# CFA_T_4L_B.net
KiCad netlist of a schematic drawn in EAGLE
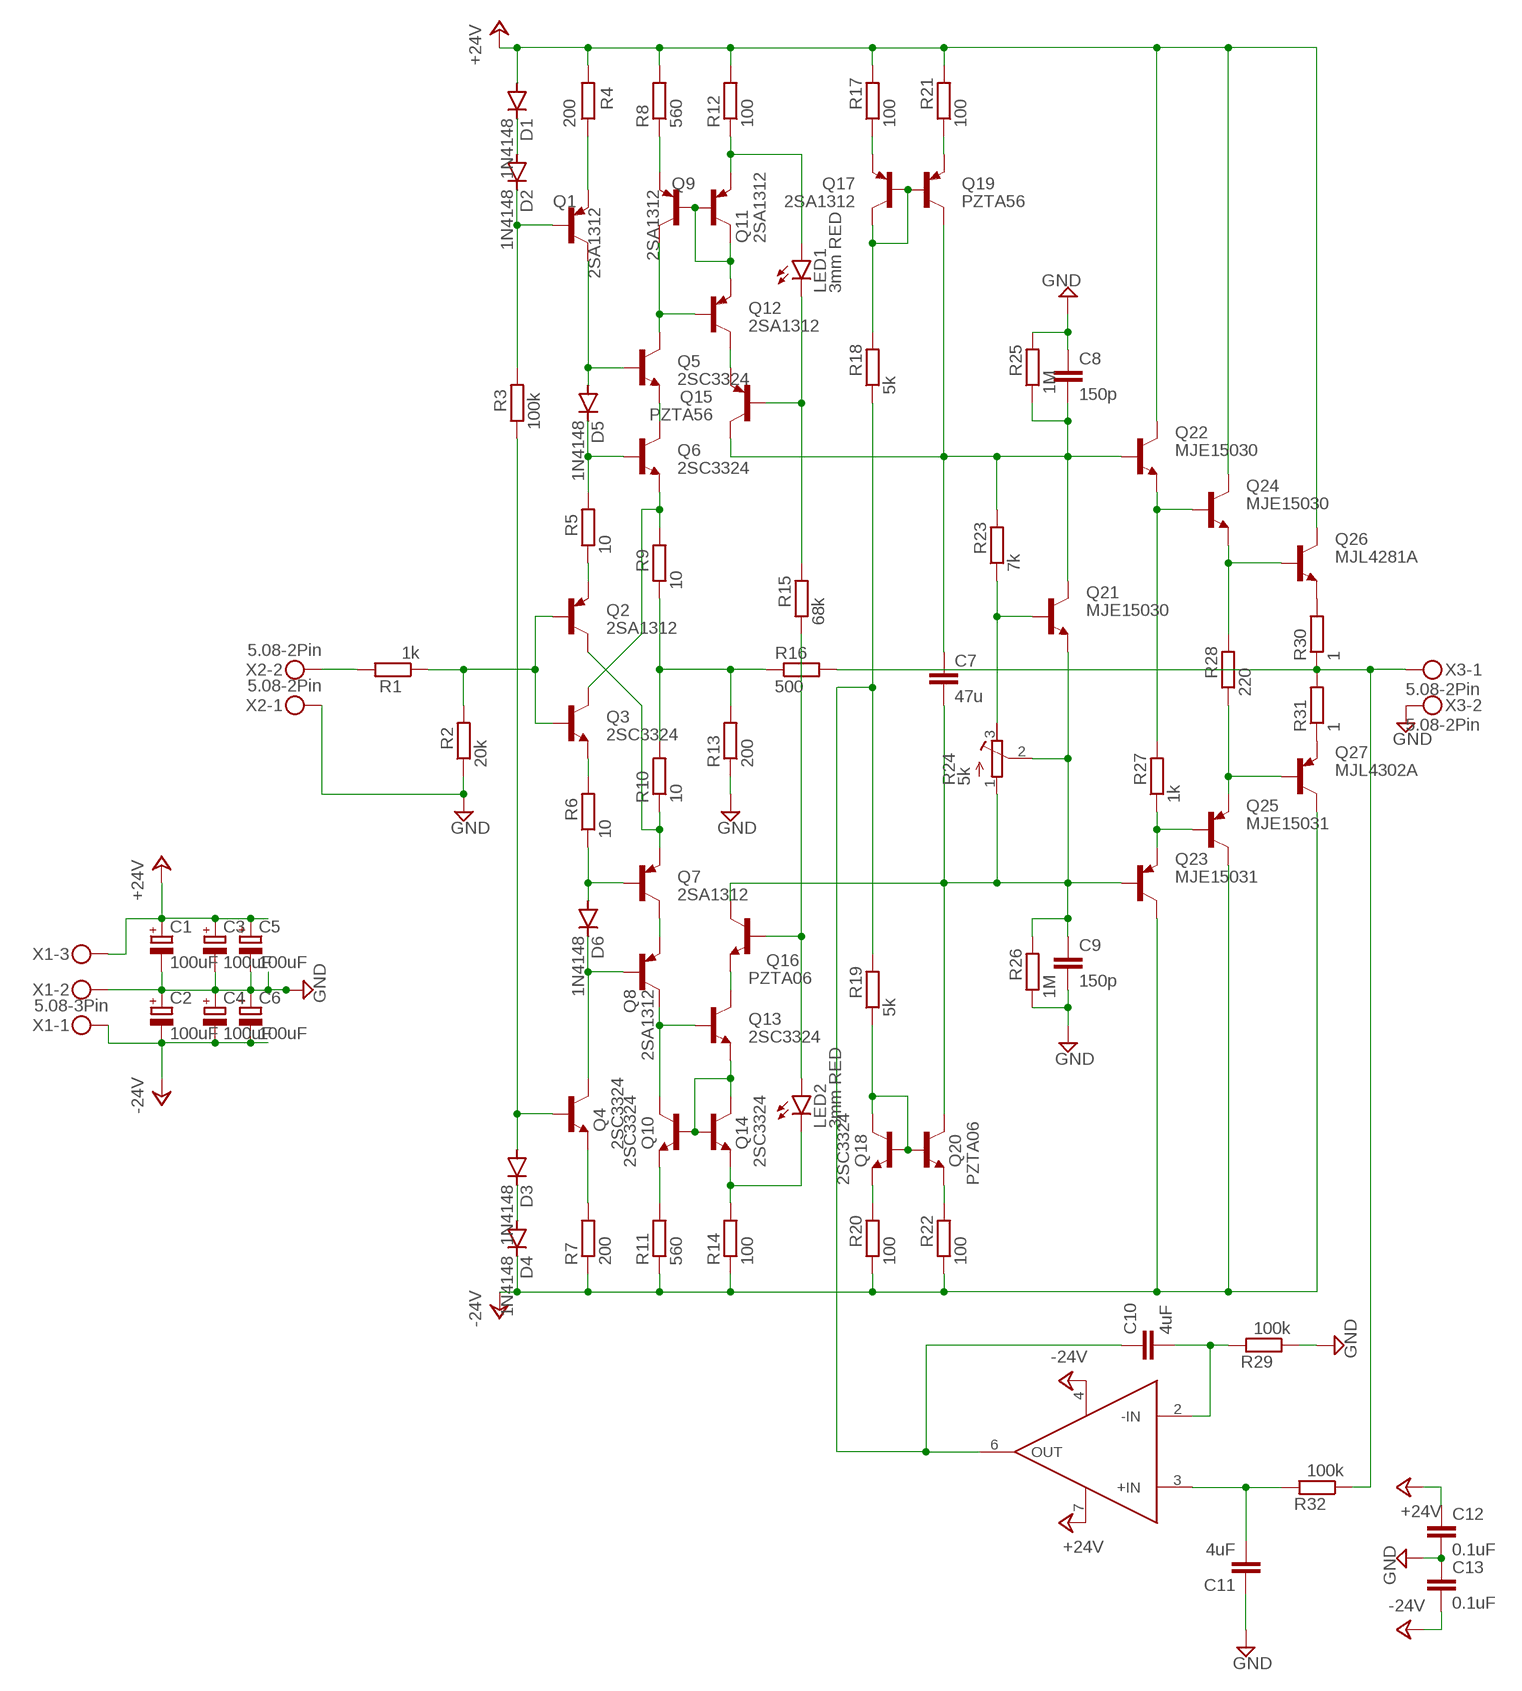
[diagram p0: schematic, sheet 1]

(export (version "E")
  (design (tool "Eeschema 10.0.6"))
  (components
    (comp (ref "C1")
      (value "100uF")
      (footprint "eagle-import:E3,5-8")
      (libsource (lib "eagle-import") (part "CPOL-EUE3.5-8"))
    )
    (comp (ref "C2")
      (value "100uF")
      (footprint "eagle-import:E3,5-8")
      (libsource (lib "eagle-import") (part "CPOL-EUE3.5-8"))
    )
    (comp (ref "C3")
      (value "100uF")
      (footprint "eagle-import:E3,5-8")
      (libsource (lib "eagle-import") (part "CPOL-EUE3.5-8"))
    )
    (comp (ref "C4")
      (value "100uF")
      (footprint "eagle-import:E3,5-8")
      (libsource (lib "eagle-import") (part "CPOL-EUE3.5-8"))
    )
    (comp (ref "C5")
      (value "100uF")
      (footprint "eagle-import:E3,5-8")
      (libsource (lib "eagle-import") (part "CPOL-EUE3.5-8"))
    )
    (comp (ref "C6")
      (value "100uF")
      (footprint "eagle-import:E3,5-8")
      (libsource (lib "eagle-import") (part "CPOL-EUE3.5-8"))
    )
    (comp (ref "C7")
      (value "47u")
      (footprint "eagle-import:C1210")
      (fields (field (name "SPICEPREFIX") "C"))
      (libsource (lib "eagle-import") (part "C-EUC1210"))
    )
    (comp (ref "C8")
      (value "150p")
      (footprint "eagle-import:C0805")
      (fields (field (name "SPICEPREFIX") "C"))
      (libsource (lib "eagle-import") (part "C-EUC0805"))
    )
    (comp (ref "C9")
      (value "150p")
      (footprint "eagle-import:C0805")
      (fields (field (name "SPICEPREFIX") "C"))
      (libsource (lib "eagle-import") (part "C-EUC0805"))
    )
    (comp (ref "C10")
      (value "4uF")
      (footprint "eagle-import:C1210")
      (fields (field (name "SPICEPREFIX") "C"))
      (libsource (lib "eagle-import") (part "C-EUC1210"))
    )
    (comp (ref "C11")
      (value "4uF")
      (footprint "eagle-import:C1210")
      (fields (field (name "SPICEPREFIX") "C"))
      (libsource (lib "eagle-import") (part "C-EUC1210"))
    )
    (comp (ref "C12")
      (value "0.1uF")
      (footprint "eagle-import:C0603K")
      (libsource (lib "eagle-import") (part "C-EUC0603K"))
    )
    (comp (ref "C13")
      (value "0.1uF")
      (footprint "eagle-import:C0603K")
      (libsource (lib "eagle-import") (part "C-EUC0603K"))
    )
    (comp (ref "D1")
      (value "1N4148")
      (footprint "eagle-import:SOD80C")
      (fields (field (name "SPICEPREFIX") "D"))
      (libsource (lib "eagle-import") (part "DIODE-SOD80C"))
    )
    (comp (ref "D2")
      (value "1N4148")
      (footprint "eagle-import:SOD80C")
      (fields (field (name "SPICEPREFIX") "D"))
      (libsource (lib "eagle-import") (part "DIODE-SOD80C"))
    )
    (comp (ref "D3")
      (value "1N4148")
      (footprint "eagle-import:SOD80C")
      (fields (field (name "SPICEPREFIX") "D"))
      (libsource (lib "eagle-import") (part "DIODE-SOD80C"))
    )
    (comp (ref "D4")
      (value "1N4148")
      (footprint "eagle-import:SOD80C")
      (fields (field (name "SPICEPREFIX") "D"))
      (libsource (lib "eagle-import") (part "DIODE-SOD80C"))
    )
    (comp (ref "D5")
      (value "1N4148")
      (footprint "eagle-import:SOD80C")
      (fields (field (name "SPICEPREFIX") "D"))
      (libsource (lib "eagle-import") (part "DIODE-SOD80C"))
    )
    (comp (ref "D6")
      (value "1N4148")
      (footprint "eagle-import:SOD80C")
      (fields (field (name "SPICEPREFIX") "D"))
      (libsource (lib "eagle-import") (part "DIODE-SOD80C"))
    )
    (comp (ref "LED1")
      (value "3mm RED")
      (footprint "eagle-import:LED3MM")
      (fields (field (name "SPICEPREFIX") "D"))
      (libsource (lib "eagle-import") (part "LED3MM"))
    )
    (comp (ref "LED2")
      (value "3mm RED")
      (footprint "eagle-import:LED3MM")
      (fields (field (name "SPICEPREFIX") "D"))
      (libsource (lib "eagle-import") (part "LED3MM"))
    )
    (comp (ref "Q1")
      (value "2SA1312")
      (footprint "eagle-import:TRANSISTOR_SOT23-BEC")
      (fields (field (name "SPICEPREFIX") "Q"))
      (libsource (lib "eagle-import") (part "TRANSISTOR_-PNP-SOT23-BECBC857C"))
    )
    (comp (ref "Q2")
      (value "2SA1312")
      (footprint "eagle-import:TRANSISTOR_SOT23-BEC")
      (fields (field (name "SPICEPREFIX") "Q"))
      (libsource (lib "eagle-import") (part "TRANSISTOR_-PNP-SOT23-BECBC857C"))
    )
    (comp (ref "Q3")
      (value "2SC3324")
      (footprint "eagle-import:TRANSISTOR_SOT23-BEC")
      (fields (field (name "SPICEPREFIX") "Q"))
      (libsource (lib "eagle-import") (part "TRANSISTOR_-NPN-SOT23-BECBC850"))
    )
    (comp (ref "Q4")
      (value "2SC3324")
      (footprint "eagle-import:TRANSISTOR_SOT23-BEC")
      (fields (field (name "SPICEPREFIX") "Q"))
      (libsource (lib "eagle-import") (part "TRANSISTOR_-NPN-SOT23-BECBC850"))
    )
    (comp (ref "Q5")
      (value "2SC3324")
      (footprint "eagle-import:TRANSISTOR_SOT23-BEC")
      (fields (field (name "SPICEPREFIX") "Q"))
      (libsource (lib "eagle-import") (part "TRANSISTOR_-NPN-SOT23-BECBC850"))
    )
    (comp (ref "Q6")
      (value "2SC3324")
      (footprint "eagle-import:TRANSISTOR_SOT23-BEC")
      (fields (field (name "SPICEPREFIX") "Q"))
      (libsource (lib "eagle-import") (part "TRANSISTOR_-NPN-SOT23-BECBC850"))
    )
    (comp (ref "Q7")
      (value "2SA1312")
      (footprint "eagle-import:TRANSISTOR_SOT23-BEC")
      (fields (field (name "SPICEPREFIX") "Q"))
      (libsource (lib "eagle-import") (part "TRANSISTOR_-PNP-SOT23-BECBC857C"))
    )
    (comp (ref "Q8")
      (value "2SA1312")
      (footprint "eagle-import:TRANSISTOR_SOT23-BEC")
      (fields (field (name "SPICEPREFIX") "Q"))
      (libsource (lib "eagle-import") (part "TRANSISTOR_-PNP-SOT23-BECBC857C"))
    )
    (comp (ref "Q9")
      (value "2SA1312")
      (footprint "eagle-import:TRANSISTOR_SOT23-BEC")
      (fields (field (name "SPICEPREFIX") "Q"))
      (libsource (lib "eagle-import") (part "TRANSISTOR_-PNP-SOT23-BECBC857C"))
    )
    (comp (ref "Q10")
      (value "2SC3324")
      (footprint "eagle-import:TRANSISTOR_SOT23-BEC")
      (fields (field (name "SPICEPREFIX") "Q"))
      (libsource (lib "eagle-import") (part "TRANSISTOR_-NPN-SOT23-BECBC850"))
    )
    (comp (ref "Q11")
      (value "2SA1312")
      (footprint "eagle-import:TRANSISTOR_SOT23-BEC")
      (fields (field (name "SPICEPREFIX") "Q"))
      (libsource (lib "eagle-import") (part "TRANSISTOR_-PNP-SOT23-BECBC857C"))
    )
    (comp (ref "Q12")
      (value "2SA1312")
      (footprint "eagle-import:TRANSISTOR_SOT23-BEC")
      (fields (field (name "SPICEPREFIX") "Q"))
      (libsource (lib "eagle-import") (part "TRANSISTOR_-PNP-SOT23-BECBC857C"))
    )
    (comp (ref "Q13")
      (value "2SC3324")
      (footprint "eagle-import:TRANSISTOR_SOT23-BEC")
      (fields (field (name "SPICEPREFIX") "Q"))
      (libsource (lib "eagle-import") (part "TRANSISTOR_-NPN-SOT23-BECBC847"))
    )
    (comp (ref "Q14")
      (value "2SC3324")
      (footprint "eagle-import:TRANSISTOR_SOT23-BEC")
      (fields (field (name "SPICEPREFIX") "Q"))
      (libsource (lib "eagle-import") (part "TRANSISTOR_-NPN-SOT23-BECBC850"))
    )
    (comp (ref "Q15")
      (value "PZTA56")
      (footprint "eagle-import:SOT223")
      (fields (field (name "SPICEPREFIX") "Q"))
      (libsource (lib "eagle-import") (part "PZTA56"))
    )
    (comp (ref "Q16")
      (value "PZTA06")
      (footprint "eagle-import:SOT223")
      (fields (field (name "SPICEPREFIX") "Q"))
      (libsource (lib "eagle-import") (part "PZTA06SOT-223"))
    )
    (comp (ref "Q17")
      (value "2SA1312")
      (footprint "eagle-import:TRANSISTOR_SOT23-BEC")
      (fields (field (name "SPICEPREFIX") "Q"))
      (libsource (lib "eagle-import") (part "TRANSISTOR_-PNP-SOT23-BECBC857C"))
    )
    (comp (ref "Q18")
      (value "2SC3324")
      (footprint "eagle-import:TRANSISTOR_SOT23-BEC")
      (fields (field (name "SPICEPREFIX") "Q"))
      (libsource (lib "eagle-import") (part "TRANSISTOR_-NPN-SOT23-BECBC850"))
    )
    (comp (ref "Q19")
      (value "PZTA56")
      (footprint "eagle-import:SOT223")
      (fields (field (name "SPICEPREFIX") "Q"))
      (libsource (lib "eagle-import") (part "PZTA56"))
    )
    (comp (ref "Q20")
      (value "PZTA06")
      (footprint "eagle-import:SOT223")
      (fields (field (name "SPICEPREFIX") "Q"))
      (libsource (lib "eagle-import") (part "PZTA06SOT-223"))
    )
    (comp (ref "Q21")
      (value "MJE15030")
      (footprint "eagle-import:TRANSISTOR_TO220KG")
      (fields (field (name "SPICEPREFIX") "Q"))
      (libsource (lib "eagle-import") (part "TRANSISTOR_MJE15030"))
    )
    (comp (ref "Q22")
      (value "MJE15030")
      (footprint "eagle-import:TRANSISTOR_TO220KG")
      (fields (field (name "SPICEPREFIX") "Q"))
      (libsource (lib "eagle-import") (part "TRANSISTOR_MJE15030"))
    )
    (comp (ref "Q23")
      (value "MJE15031")
      (footprint "eagle-import:TRANSISTOR_TO220KG")
      (fields (field (name "SPICEPREFIX") "Q"))
      (libsource (lib "eagle-import") (part "TRANSISTOR_MJE15031"))
    )
    (comp (ref "Q24")
      (value "MJE15030")
      (footprint "eagle-import:TRANSISTOR_TO220KG")
      (fields (field (name "SPICEPREFIX") "Q"))
      (libsource (lib "eagle-import") (part "TRANSISTOR_MJE15030"))
    )
    (comp (ref "Q25")
      (value "MJE15031")
      (footprint "eagle-import:TRANSISTOR_TO220KG")
      (fields (field (name "SPICEPREFIX") "Q"))
      (libsource (lib "eagle-import") (part "TRANSISTOR_MJE15031"))
    )
    (comp (ref "Q26")
      (value "MJL4281A")
      (footprint "eagle-import:TO264_TO-264")
      (fields (field (name "SPICEPREFIX") "Q"))
      (libsource (lib "eagle-import") (part "TO264_MJL4281"))
    )
    (comp (ref "Q27")
      (value "MJL4302A")
      (footprint "eagle-import:TO264_TO-264")
      (fields (field (name "SPICEPREFIX") "Q"))
      (libsource (lib "eagle-import") (part "TO264_MJL4302"))
    )
    (comp (ref "R1")
      (value "1k")
      (footprint "eagle-import:MINI_MELF-0204W")
      (fields (field (name "SPICEPREFIX") "R"))
      (libsource (lib "eagle-import") (part "R-EU_MELF0204W"))
    )
    (comp (ref "R2")
      (value "20k")
      (footprint "eagle-import:MINI_MELF-0204W")
      (fields (field (name "SPICEPREFIX") "R"))
      (libsource (lib "eagle-import") (part "R-EU_MELF0204W"))
    )
    (comp (ref "R3")
      (value "100k")
      (footprint "eagle-import:MINI_MELF-0204W")
      (fields (field (name "SPICEPREFIX") "R"))
      (libsource (lib "eagle-import") (part "R-EU_MELF0204W"))
    )
    (comp (ref "R4")
      (value "200")
      (footprint "eagle-import:MINI_MELF-0204W")
      (fields (field (name "SPICEPREFIX") "R"))
      (libsource (lib "eagle-import") (part "R-EU_MELF0204W"))
    )
    (comp (ref "R5")
      (value "10")
      (footprint "eagle-import:MINI_MELF-0204W")
      (fields (field (name "SPICEPREFIX") "R"))
      (libsource (lib "eagle-import") (part "R-EU_MELF0204W"))
    )
    (comp (ref "R6")
      (value "10")
      (footprint "eagle-import:MINI_MELF-0204W")
      (fields (field (name "SPICEPREFIX") "R"))
      (libsource (lib "eagle-import") (part "R-EU_MELF0204W"))
    )
    (comp (ref "R7")
      (value "200")
      (footprint "eagle-import:MINI_MELF-0204W")
      (fields (field (name "SPICEPREFIX") "R"))
      (libsource (lib "eagle-import") (part "R-EU_MELF0204W"))
    )
    (comp (ref "R8")
      (value "560")
      (footprint "eagle-import:MINI_MELF-0204W")
      (fields (field (name "SPICEPREFIX") "R"))
      (libsource (lib "eagle-import") (part "R-EU_MELF0204W"))
    )
    (comp (ref "R9")
      (value "10")
      (footprint "eagle-import:MINI_MELF-0204W")
      (fields (field (name "SPICEPREFIX") "R"))
      (libsource (lib "eagle-import") (part "R-EU_MELF0204W"))
    )
    (comp (ref "R10")
      (value "10")
      (footprint "eagle-import:MINI_MELF-0204W")
      (fields (field (name "SPICEPREFIX") "R"))
      (libsource (lib "eagle-import") (part "R-EU_MELF0204W"))
    )
    (comp (ref "R11")
      (value "560")
      (footprint "eagle-import:MINI_MELF-0204W")
      (fields (field (name "SPICEPREFIX") "R"))
      (libsource (lib "eagle-import") (part "R-EU_MELF0204W"))
    )
    (comp (ref "R12")
      (value "100")
      (footprint "eagle-import:MINI_MELF-0204W")
      (fields (field (name "SPICEPREFIX") "R"))
      (libsource (lib "eagle-import") (part "R-EU_MELF0204W"))
    )
    (comp (ref "R13")
      (value "200")
      (footprint "eagle-import:MINI_MELF-0204W")
      (fields (field (name "SPICEPREFIX") "R"))
      (libsource (lib "eagle-import") (part "R-EU_MELF0204W"))
    )
    (comp (ref "R14")
      (value "100")
      (footprint "eagle-import:MINI_MELF-0204W")
      (fields (field (name "SPICEPREFIX") "R"))
      (libsource (lib "eagle-import") (part "R-EU_MELF0204W"))
    )
    (comp (ref "R15")
      (value "68k")
      (footprint "eagle-import:MINI_MELF-0204W")
      (fields (field (name "SPICEPREFIX") "R"))
      (libsource (lib "eagle-import") (part "R-EU_MELF0204W"))
    )
    (comp (ref "R16")
      (value "500")
      (footprint "eagle-import:MINI_MELF-0204W")
      (fields (field (name "SPICEPREFIX") "R"))
      (libsource (lib "eagle-import") (part "R-EU_MELF0204W"))
    )
    (comp (ref "R17")
      (value "100")
      (footprint "eagle-import:MINI_MELF-0204W")
      (fields (field (name "SPICEPREFIX") "R"))
      (libsource (lib "eagle-import") (part "R-EU_MELF0204W"))
    )
    (comp (ref "R18")
      (value "5k")
      (footprint "eagle-import:MINI_MELF-0204W")
      (fields (field (name "SPICEPREFIX") "R"))
      (libsource (lib "eagle-import") (part "R-EU_MELF0204W"))
    )
    (comp (ref "R19")
      (value "5k")
      (footprint "eagle-import:MINI_MELF-0204W")
      (fields (field (name "SPICEPREFIX") "R"))
      (libsource (lib "eagle-import") (part "R-EU_MELF0204W"))
    )
    (comp (ref "R20")
      (value "100")
      (footprint "eagle-import:MINI_MELF-0204W")
      (fields (field (name "SPICEPREFIX") "R"))
      (libsource (lib "eagle-import") (part "R-EU_MELF0204W"))
    )
    (comp (ref "R21")
      (value "100")
      (footprint "eagle-import:MINI_MELF-0204W")
      (fields (field (name "SPICEPREFIX") "R"))
      (libsource (lib "eagle-import") (part "R-EU_MELF0204W"))
    )
    (comp (ref "R22")
      (value "100")
      (footprint "eagle-import:MINI_MELF-0204W")
      (fields (field (name "SPICEPREFIX") "R"))
      (libsource (lib "eagle-import") (part "R-EU_MELF0204W"))
    )
    (comp (ref "R23")
      (value "7k")
      (footprint "eagle-import:MINI_MELF-0204W")
      (fields (field (name "SPICEPREFIX") "R"))
      (libsource (lib "eagle-import") (part "R-EU_MELF0204W"))
    )
    (comp (ref "R24")
      (value "5k")
      (footprint "eagle-import:RTRIM3296W")
      (fields (field (name "SPICEPREFIX") "Z"))
      (libsource (lib "eagle-import") (part "R-TRIMM3296W"))
    )
    (comp (ref "R25")
      (value "1M")
      (footprint "eagle-import:MINI_MELF-0204W")
      (fields (field (name "SPICEPREFIX") "R"))
      (libsource (lib "eagle-import") (part "R-EU_MELF0204W"))
    )
    (comp (ref "R26")
      (value "1M")
      (footprint "eagle-import:MINI_MELF-0204W")
      (fields (field (name "SPICEPREFIX") "R"))
      (libsource (lib "eagle-import") (part "R-EU_MELF0204W"))
    )
    (comp (ref "R27")
      (value "1k")
      (footprint "eagle-import:MINI_MELF-0204W")
      (fields (field (name "SPICEPREFIX") "R"))
      (libsource (lib "eagle-import") (part "R-EU_MELF0204W"))
    )
    (comp (ref "R28")
      (value "220")
      (footprint "eagle-import:MINI_MELF-0204W")
      (fields (field (name "SPICEPREFIX") "R"))
      (libsource (lib "eagle-import") (part "R-EU_MELF0204W"))
    )
    (comp (ref "R29")
      (value "100k")
      (footprint "eagle-import:MINI_MELF-0204W")
      (fields (field (name "SPICEPREFIX") "R"))
      (libsource (lib "eagle-import") (part "R-EU_MELF0204W"))
    )
    (comp (ref "R30")
      (value "1")
      (footprint "eagle-import:TO220-2")
      (fields (field (name "SPICEPREFIX") "R"))
      (libsource (lib "eagle-import") (part "R-EU_TO220"))
    )
    (comp (ref "R31")
      (value "1")
      (footprint "eagle-import:TO220-2")
      (fields (field (name "SPICEPREFIX") "R"))
      (libsource (lib "eagle-import") (part "R-EU_TO220"))
    )
    (comp (ref "R32")
      (value "100k")
      (footprint "eagle-import:MINI_MELF-0204W")
      (fields (field (name "SPICEPREFIX") "R"))
      (libsource (lib "eagle-import") (part "R-EU_MELF0204W"))
    )
    (comp (ref "U1")
      (value "OP27")
      (footprint "eagle-import:DIL08")
      (libsource (lib "eagle-import") (part "OPA627BP"))
    )
    (comp (ref "X1")
      (value "5.08-3Pin")
      (footprint "eagle-import:CON-PHOENIX-508_MKDSN1,5_3-5,08")
      (libsource (lib "eagle-import") (part "CON-PHOENIX-508_MKDSN1,5/3-5,08"))
    )
    (comp (ref "X2")
      (value "5.08-2Pin")
      (footprint "eagle-import:CON-PHOENIX-508_MKDSN1,5_2-5,08")
      (libsource (lib "eagle-import") (part "CON-PHOENIX-508_MKDSN1,5/2-5,08"))
    )
    (comp (ref "X3")
      (value "5.08-2Pin")
      (footprint "eagle-import:CON-PHOENIX-508_MKDSN1,5_2-5,08")
      (libsource (lib "eagle-import") (part "CON-PHOENIX-508_MKDSN1,5/2-5,08"))
    )
  )
  (nets
    (net (code "1") (name "+24V") (class "Default")
      (node (ref "C1") (pin "+") (pinfunction "+_+") (pintype "passive"))
      (node (ref "C12") (pin "1") (pinfunction "1_1") (pintype "passive"))
      (node (ref "C3") (pin "+") (pinfunction "+_+") (pintype "passive"))
      (node (ref "C5") (pin "+") (pinfunction "+_+") (pintype "passive"))
      (node (ref "D1") (pin "A") (pinfunction "A_A") (pintype "passive"))
      (node (ref "Q22") (pin "2") (pinfunction "C_2") (pintype "passive"))
      (node (ref "Q24") (pin "2") (pinfunction "C_2") (pintype "passive"))
      (node (ref "Q26") (pin "C") (pinfunction "C_C") (pintype "passive"))
      (node (ref "R12") (pin "2") (pinfunction "2_2") (pintype "passive"))
      (node (ref "R17") (pin "2") (pinfunction "2_2") (pintype "passive"))
      (node (ref "R21") (pin "2") (pinfunction "2_2") (pintype "passive"))
      (node (ref "R4") (pin "2") (pinfunction "2_2") (pintype "passive"))
      (node (ref "R8") (pin "2") (pinfunction "2_2") (pintype "passive"))
      (node (ref "U1") (pin "7") (pinfunction "V+_7") (pintype "bidirectional"))
      (node (ref "X1") (pin "3") (pinfunction "KL_3") (pintype "passive"))
    )
    (net (code "2") (name "-24V") (class "Default")
      (node (ref "C13") (pin "2") (pinfunction "2_2") (pintype "passive"))
      (node (ref "C2") (pin "-") (pinfunction "-_-") (pintype "passive"))
      (node (ref "C4") (pin "-") (pinfunction "-_-") (pintype "passive"))
      (node (ref "C6") (pin "-") (pinfunction "-_-") (pintype "passive"))
      (node (ref "D4") (pin "C") (pinfunction "C_C") (pintype "passive"))
      (node (ref "Q23") (pin "2") (pinfunction "C_2") (pintype "passive"))
      (node (ref "Q25") (pin "2") (pinfunction "C_2") (pintype "passive"))
      (node (ref "Q27") (pin "C") (pinfunction "C_C") (pintype "passive"))
      (node (ref "R11") (pin "1") (pinfunction "1_1") (pintype "passive"))
      (node (ref "R14") (pin "1") (pinfunction "1_1") (pintype "passive"))
      (node (ref "R20") (pin "1") (pinfunction "1_1") (pintype "passive"))
      (node (ref "R22") (pin "1") (pinfunction "1_1") (pintype "passive"))
      (node (ref "R7") (pin "1") (pinfunction "1_1") (pintype "passive"))
      (node (ref "U1") (pin "4") (pinfunction "V-_4") (pintype "bidirectional"))
      (node (ref "X1") (pin "1") (pinfunction "KL_1") (pintype "passive"))
    )
    (net (code "3") (name "GND") (class "Default")
      (node (ref "C1") (pin "-") (pinfunction "-_-") (pintype "passive"))
      (node (ref "C11") (pin "1") (pinfunction "1_1") (pintype "passive"))
      (node (ref "C12") (pin "2") (pinfunction "2_2") (pintype "passive"))
      (node (ref "C13") (pin "1") (pinfunction "1_1") (pintype "passive"))
      (node (ref "C2") (pin "+") (pinfunction "+_+") (pintype "passive"))
      (node (ref "C3") (pin "-") (pinfunction "-_-") (pintype "passive"))
      (node (ref "C4") (pin "+") (pinfunction "+_+") (pintype "passive"))
      (node (ref "C5") (pin "-") (pinfunction "-_-") (pintype "passive"))
      (node (ref "C6") (pin "+") (pinfunction "+_+") (pintype "passive"))
      (node (ref "C8") (pin "1") (pinfunction "1_1") (pintype "passive"))
      (node (ref "C9") (pin "2") (pinfunction "2_2") (pintype "passive"))
      (node (ref "R13") (pin "1") (pinfunction "1_1") (pintype "passive"))
      (node (ref "R2") (pin "1") (pinfunction "1_1") (pintype "passive"))
      (node (ref "R25") (pin "2") (pinfunction "2_2") (pintype "passive"))
      (node (ref "R26") (pin "1") (pinfunction "1_1") (pintype "passive"))
      (node (ref "R29") (pin "1") (pinfunction "1_1") (pintype "passive"))
      (node (ref "X1") (pin "2") (pinfunction "KL_2") (pintype "passive"))
      (node (ref "X2") (pin "1") (pinfunction "KL_1") (pintype "passive"))
      (node (ref "X3") (pin "2") (pinfunction "KL_2") (pintype "passive"))
    )
    (net (code "4") (name "Net-(D1-PadC)") (class "Default")
      (node (ref "D1") (pin "C") (pinfunction "C_C") (pintype "passive"))
      (node (ref "D2") (pin "A") (pinfunction "A_A") (pintype "passive"))
    )
    (net (code "5") (name "Net-(D2-PadC)") (class "Default")
      (node (ref "D2") (pin "C") (pinfunction "C_C") (pintype "passive"))
      (node (ref "Q1") (pin "B") (pinfunction "B_B") (pintype "passive"))
      (node (ref "R3") (pin "2") (pinfunction "2_2") (pintype "passive"))
    )
    (net (code "6") (name "Net-(D3-PadA)") (class "Default")
      (node (ref "D3") (pin "A") (pinfunction "A_A") (pintype "passive"))
      (node (ref "Q4") (pin "B") (pinfunction "B_B") (pintype "passive"))
      (node (ref "R3") (pin "1") (pinfunction "1_1") (pintype "passive"))
    )
    (net (code "7") (name "Net-(D3-PadC)") (class "Default")
      (node (ref "D3") (pin "C") (pinfunction "C_C") (pintype "passive"))
      (node (ref "D4") (pin "A") (pinfunction "A_A") (pintype "passive"))
    )
    (net (code "8") (name "Net-(D5-PadA)") (class "Default")
      (node (ref "D5") (pin "A") (pinfunction "A_A") (pintype "passive"))
      (node (ref "Q1") (pin "C") (pinfunction "C_C") (pintype "passive"))
      (node (ref "Q5") (pin "B") (pinfunction "B_B") (pintype "passive"))
    )
    (net (code "9") (name "Net-(D5-PadC)") (class "Default")
      (node (ref "D5") (pin "C") (pinfunction "C_C") (pintype "passive"))
      (node (ref "Q6") (pin "B") (pinfunction "B_B") (pintype "passive"))
      (node (ref "R5") (pin "2") (pinfunction "2_2") (pintype "passive"))
    )
    (net (code "10") (name "Net-(D6-PadA)") (class "Default")
      (node (ref "D6") (pin "A") (pinfunction "A_A") (pintype "passive"))
      (node (ref "Q7") (pin "B") (pinfunction "B_B") (pintype "passive"))
      (node (ref "R6") (pin "1") (pinfunction "1_1") (pintype "passive"))
    )
    (net (code "11") (name "Net-(D6-PadC)") (class "Default")
      (node (ref "D6") (pin "C") (pinfunction "C_C") (pintype "passive"))
      (node (ref "Q4") (pin "C") (pinfunction "C_C") (pintype "passive"))
      (node (ref "Q8") (pin "B") (pinfunction "B_B") (pintype "passive"))
    )
    (net (code "12") (name "Net-(LED1-C)") (class "Default")
      (node (ref "LED1") (pin "K") (pinfunction "C_K") (pintype "passive"))
      (node (ref "Q15") (pin "1") (pinfunction "B_1") (pintype "passive"))
      (node (ref "R15") (pin "2") (pinfunction "2_2") (pintype "passive"))
    )
    (net (code "13") (name "Net-(LED1-PadA)") (class "Default")
      (node (ref "LED1") (pin "A") (pinfunction "A_A") (pintype "passive"))
      (node (ref "Q11") (pin "E") (pinfunction "E_E") (pintype "passive"))
      (node (ref "R12") (pin "1") (pinfunction "1_1") (pintype "passive"))
    )
    (net (code "14") (name "Net-(LED2-C)") (class "Default")
      (node (ref "LED2") (pin "K") (pinfunction "C_K") (pintype "passive"))
      (node (ref "Q14") (pin "E") (pinfunction "E_E") (pintype "passive"))
      (node (ref "R14") (pin "2") (pinfunction "2_2") (pintype "passive"))
    )
    (net (code "15") (name "Net-(Q1-PadE)") (class "Default")
      (node (ref "Q1") (pin "E") (pinfunction "E_E") (pintype "passive"))
      (node (ref "R4") (pin "1") (pinfunction "1_1") (pintype "passive"))
    )
    (net (code "16") (name "Net-(Q2-PadB)") (class "Default")
      (node (ref "Q2") (pin "B") (pinfunction "B_B") (pintype "passive"))
      (node (ref "Q3") (pin "B") (pinfunction "B_B") (pintype "passive"))
      (node (ref "R1") (pin "1") (pinfunction "1_1") (pintype "passive"))
      (node (ref "R2") (pin "2") (pinfunction "2_2") (pintype "passive"))
    )
    (net (code "17") (name "Net-(Q2-PadC)") (class "Default")
      (node (ref "Q2") (pin "C") (pinfunction "C_C") (pintype "passive"))
      (node (ref "Q7") (pin "E") (pinfunction "E_E") (pintype "passive"))
      (node (ref "R10") (pin "1") (pinfunction "1_1") (pintype "passive"))
    )
    (net (code "18") (name "Net-(Q2-PadE)") (class "Default")
      (node (ref "Q2") (pin "E") (pinfunction "E_E") (pintype "passive"))
      (node (ref "R5") (pin "1") (pinfunction "1_1") (pintype "passive"))
    )
    (net (code "19") (name "Net-(Q3-PadC)") (class "Default")
      (node (ref "Q3") (pin "C") (pinfunction "C_C") (pintype "passive"))
      (node (ref "Q6") (pin "E") (pinfunction "E_E") (pintype "passive"))
      (node (ref "R9") (pin "2") (pinfunction "2_2") (pintype "passive"))
    )
    (net (code "20") (name "Net-(Q3-PadE)") (class "Default")
      (node (ref "Q3") (pin "E") (pinfunction "E_E") (pintype "passive"))
      (node (ref "R6") (pin "2") (pinfunction "2_2") (pintype "passive"))
    )
    (net (code "21") (name "Net-(Q4-PadE)") (class "Default")
      (node (ref "Q4") (pin "E") (pinfunction "E_E") (pintype "passive"))
      (node (ref "R7") (pin "2") (pinfunction "2_2") (pintype "passive"))
    )
    (net (code "22") (name "Net-(Q5-PadE)") (class "Default")
      (node (ref "Q5") (pin "E") (pinfunction "E_E") (pintype "passive"))
      (node (ref "Q6") (pin "C") (pinfunction "C_C") (pintype "passive"))
    )
    (net (code "23") (name "Net-(Q7-PadC)") (class "Default")
      (node (ref "Q7") (pin "C") (pinfunction "C_C") (pintype "passive"))
      (node (ref "Q8") (pin "E") (pinfunction "E_E") (pintype "passive"))
    )
    (net (code "24") (name "Net-(Q9-PadE)") (class "Default")
      (node (ref "Q9") (pin "E") (pinfunction "E_E") (pintype "passive"))
      (node (ref "R8") (pin "1") (pinfunction "1_1") (pintype "passive"))
    )
    (net (code "25") (name "Net-(Q10-PadB)") (class "Default")
      (node (ref "Q10") (pin "B") (pinfunction "B_B") (pintype "passive"))
      (node (ref "Q13") (pin "E") (pinfunction "E_E") (pintype "passive"))
      (node (ref "Q14") (pin "B") (pinfunction "B_B") (pintype "passive"))
      (node (ref "Q14") (pin "C") (pinfunction "C_C") (pintype "passive"))
    )
    (net (code "26") (name "Net-(Q10-PadC)") (class "Default")
      (node (ref "Q10") (pin "C") (pinfunction "C_C") (pintype "passive"))
      (node (ref "Q13") (pin "B") (pinfunction "B_B") (pintype "passive"))
      (node (ref "Q8") (pin "C") (pinfunction "C_C") (pintype "passive"))
    )
    (net (code "27") (name "Net-(Q10-PadE)") (class "Default")
      (node (ref "Q10") (pin "E") (pinfunction "E_E") (pintype "passive"))
      (node (ref "R11") (pin "2") (pinfunction "2_2") (pintype "passive"))
    )
    (net (code "28") (name "Net-(Q11-PadB)") (class "Default")
      (node (ref "Q11") (pin "B") (pinfunction "B_B") (pintype "passive"))
      (node (ref "Q11") (pin "C") (pinfunction "C_C") (pintype "passive"))
      (node (ref "Q12") (pin "E") (pinfunction "E_E") (pintype "passive"))
      (node (ref "Q9") (pin "B") (pinfunction "B_B") (pintype "passive"))
    )
    (net (code "29") (name "Net-(Q12-PadB)") (class "Default")
      (node (ref "Q12") (pin "B") (pinfunction "B_B") (pintype "passive"))
      (node (ref "Q5") (pin "C") (pinfunction "C_C") (pintype "passive"))
      (node (ref "Q9") (pin "C") (pinfunction "C_C") (pintype "passive"))
    )
    (net (code "30") (name "Net-(Q15-E)") (class "Default")
      (node (ref "Q12") (pin "C") (pinfunction "C_C") (pintype "passive"))
      (node (ref "Q15") (pin "3") (pinfunction "E_3") (pintype "passive"))
    )
    (net (code "31") (name "Net-(Q16-B)") (class "Default")
      (node (ref "LED2") (pin "A") (pinfunction "A_A") (pintype "passive"))
      (node (ref "Q16") (pin "1") (pinfunction "B_1") (pintype "passive"))
      (node (ref "R15") (pin "1") (pinfunction "1_1") (pintype "passive"))
    )
    (net (code "32") (name "Net-(Q16-E)") (class "Default")
      (node (ref "Q13") (pin "C") (pinfunction "C_C") (pintype "passive"))
      (node (ref "Q16") (pin "3") (pinfunction "E_3") (pintype "passive"))
    )
    (net (code "33") (name "Net-(Q17-PadE)") (class "Default")
      (node (ref "Q17") (pin "E") (pinfunction "E_E") (pintype "passive"))
      (node (ref "R17") (pin "1") (pinfunction "1_1") (pintype "passive"))
    )
    (net (code "34") (name "Net-(Q18-PadE)") (class "Default")
      (node (ref "Q18") (pin "E") (pinfunction "E_E") (pintype "passive"))
      (node (ref "R20") (pin "2") (pinfunction "2_2") (pintype "passive"))
    )
    (net (code "35") (name "Net-(Q19-B)") (class "Default")
      (node (ref "Q17") (pin "B") (pinfunction "B_B") (pintype "passive"))
      (node (ref "Q17") (pin "C") (pinfunction "C_C") (pintype "passive"))
      (node (ref "Q19") (pin "1") (pinfunction "B_1") (pintype "passive"))
      (node (ref "R18") (pin "2") (pinfunction "2_2") (pintype "passive"))
    )
    (net (code "36") (name "Net-(Q19-E)") (class "Default")
      (node (ref "Q19") (pin "3") (pinfunction "E_3") (pintype "passive"))
      (node (ref "R21") (pin "1") (pinfunction "1_1") (pintype "passive"))
    )
    (net (code "37") (name "Net-(Q20-B)") (class "Default")
      (node (ref "Q18") (pin "B") (pinfunction "B_B") (pintype "passive"))
      (node (ref "Q18") (pin "C") (pinfunction "C_C") (pintype "passive"))
      (node (ref "Q20") (pin "1") (pinfunction "B_1") (pintype "passive"))
      (node (ref "R19") (pin "1") (pinfunction "1_1") (pintype "passive"))
    )
    (net (code "38") (name "Net-(Q20-E)") (class "Default")
      (node (ref "Q20") (pin "3") (pinfunction "E_3") (pintype "passive"))
      (node (ref "R22") (pin "2") (pinfunction "2_2") (pintype "passive"))
    )
    (net (code "39") (name "Net-(Q21-B)") (class "Default")
      (node (ref "Q21") (pin "1") (pinfunction "B_1") (pintype "passive"))
      (node (ref "R23") (pin "1") (pinfunction "1_1") (pintype "passive"))
      (node (ref "R24") (pin "3") (pinfunction "E_3") (pintype "passive"))
    )
    (net (code "40") (name "Net-(Q21-C)") (class "Default")
      (node (ref "C7") (pin "1") (pinfunction "1_1") (pintype "passive"))
      (node (ref "C8") (pin "2") (pinfunction "2_2") (pintype "passive"))
      (node (ref "Q15") (pin "2") (pinfunction "C_2") (pintype "passive"))
      (node (ref "Q15") (pin "4") (pinfunction "C_4") (pintype "passive"))
      (node (ref "Q19") (pin "2") (pinfunction "C_2") (pintype "passive"))
      (node (ref "Q19") (pin "4") (pinfunction "C_4") (pintype "passive"))
      (node (ref "Q21") (pin "2") (pinfunction "C_2") (pintype "passive"))
      (node (ref "Q22") (pin "1") (pinfunction "B_1") (pintype "passive"))
      (node (ref "R23") (pin "2") (pinfunction "2_2") (pintype "passive"))
      (node (ref "R25") (pin "1") (pinfunction "1_1") (pintype "passive"))
    )
    (net (code "41") (name "Net-(Q21-E)") (class "Default")
      (node (ref "C7") (pin "2") (pinfunction "2_2") (pintype "passive"))
      (node (ref "C9") (pin "1") (pinfunction "1_1") (pintype "passive"))
      (node (ref "Q16") (pin "2") (pinfunction "C_2") (pintype "passive"))
      (node (ref "Q16") (pin "4") (pinfunction "C_4") (pintype "passive"))
      (node (ref "Q20") (pin "2") (pinfunction "C_2") (pintype "passive"))
      (node (ref "Q20") (pin "4") (pinfunction "C_4") (pintype "passive"))
      (node (ref "Q21") (pin "3") (pinfunction "E_3") (pintype "passive"))
      (node (ref "Q23") (pin "1") (pinfunction "B_1") (pintype "passive"))
      (node (ref "R24") (pin "1") (pinfunction "A_1") (pintype "passive"))
      (node (ref "R24") (pin "2") (pinfunction "S_2") (pintype "passive"))
      (node (ref "R26") (pin "2") (pinfunction "2_2") (pintype "passive"))
    )
    (net (code "42") (name "Net-(Q22-E)") (class "Default")
      (node (ref "Q22") (pin "3") (pinfunction "E_3") (pintype "passive"))
      (node (ref "Q24") (pin "1") (pinfunction "B_1") (pintype "passive"))
      (node (ref "R27") (pin "2") (pinfunction "2_2") (pintype "passive"))
    )
    (net (code "43") (name "Net-(Q23-E)") (class "Default")
      (node (ref "Q23") (pin "3") (pinfunction "E_3") (pintype "passive"))
      (node (ref "Q25") (pin "1") (pinfunction "B_1") (pintype "passive"))
      (node (ref "R27") (pin "1") (pinfunction "1_1") (pintype "passive"))
    )
    (net (code "44") (name "Net-(Q24-E)") (class "Default")
      (node (ref "Q24") (pin "3") (pinfunction "E_3") (pintype "passive"))
      (node (ref "Q26") (pin "B") (pinfunction "B_B") (pintype "passive"))
      (node (ref "R28") (pin "2") (pinfunction "2_2") (pintype "passive"))
    )
    (net (code "45") (name "Net-(Q25-E)") (class "Default")
      (node (ref "Q25") (pin "3") (pinfunction "E_3") (pintype "passive"))
      (node (ref "Q27") (pin "B") (pinfunction "B_B") (pintype "passive"))
      (node (ref "R28") (pin "1") (pinfunction "1_1") (pintype "passive"))
    )
    (net (code "46") (name "Net-(Q26-PadE)") (class "Default")
      (node (ref "Q26") (pin "E") (pinfunction "E_E") (pintype "passive"))
      (node (ref "R30") (pin "2") (pinfunction "2_2") (pintype "passive"))
    )
    (net (code "47") (name "Net-(Q27-PadE)") (class "Default")
      (node (ref "Q27") (pin "E") (pinfunction "E_E") (pintype "passive"))
      (node (ref "R31") (pin "1") (pinfunction "1_1") (pintype "passive"))
    )
    (net (code "48") (name "Net-(R10-Pad2)") (class "Default")
      (node (ref "R10") (pin "2") (pinfunction "2_2") (pintype "passive"))
      (node (ref "R13") (pin "2") (pinfunction "2_2") (pintype "passive"))
      (node (ref "R16") (pin "1") (pinfunction "1_1") (pintype "passive"))
      (node (ref "R9") (pin "1") (pinfunction "1_1") (pintype "passive"))
    )
    (net (code "49") (name "Net-(U1A-+IN)") (class "Default")
      (node (ref "C11") (pin "2") (pinfunction "2_2") (pintype "passive"))
      (node (ref "R32") (pin "2") (pinfunction "2_2") (pintype "passive"))
      (node (ref "U1") (pin "3") (pinfunction "+IN_3") (pintype "bidirectional"))
    )
    (net (code "50") (name "Net-(U1A--IN)") (class "Default")
      (node (ref "C10") (pin "2") (pinfunction "2_2") (pintype "passive"))
      (node (ref "R29") (pin "2") (pinfunction "2_2") (pintype "passive"))
      (node (ref "U1") (pin "2") (pinfunction "-IN_2") (pintype "bidirectional"))
    )
    (net (code "51") (name "Net-(U1A-OUT)") (class "Default")
      (node (ref "C10") (pin "1") (pinfunction "1_1") (pintype "passive"))
      (node (ref "R18") (pin "1") (pinfunction "1_1") (pintype "passive"))
      (node (ref "R19") (pin "2") (pinfunction "2_2") (pintype "passive"))
      (node (ref "U1") (pin "6") (pinfunction "OUT_6") (pintype "bidirectional"))
    )
    (net (code "52") (name "Net-(X2B-KL)") (class "Default")
      (node (ref "R1") (pin "2") (pinfunction "2_2") (pintype "passive"))
      (node (ref "X2") (pin "2") (pinfunction "KL_2") (pintype "passive"))
    )
    (net (code "53") (name "Net-(X3A-KL)") (class "Default")
      (node (ref "R16") (pin "2") (pinfunction "2_2") (pintype "passive"))
      (node (ref "R30") (pin "1") (pinfunction "1_1") (pintype "passive"))
      (node (ref "R31") (pin "2") (pinfunction "2_2") (pintype "passive"))
      (node (ref "R32") (pin "1") (pinfunction "1_1") (pintype "passive"))
      (node (ref "X3") (pin "1") (pinfunction "KL_1") (pintype "passive"))
    )
  )
)
